# smartbedlight2_5.net
KiCad netlist of a schematic drawn in EAGLE
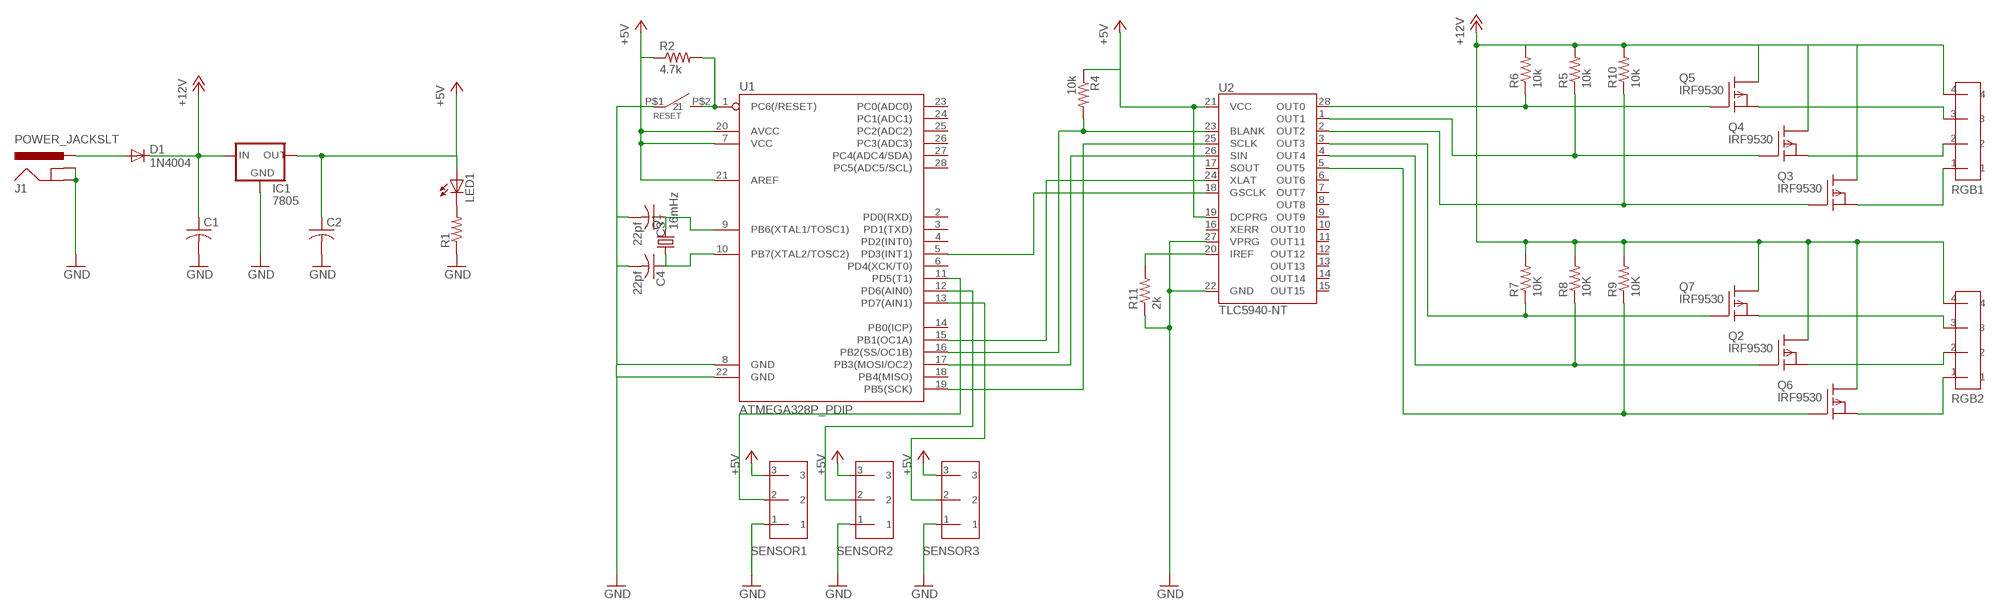
[diagram p0: schematic, sheet 1]

(export (version "E")
  (design (tool "Eeschema 10.0.6"))
  (components
    (comp (ref "C1")
      (value "C-US025-030X050")
      (footprint "eagle-import:C025-030X050")
      (libsource (lib "eagle-import") (part "C-US025-030X050"))
    )
    (comp (ref "C2")
      (value "C-US025-030X050")
      (footprint "eagle-import:C025-030X050")
      (libsource (lib "eagle-import") (part "C-US025-030X050"))
    )
    (comp (ref "C3")
      (value "22pf")
      (footprint "eagle-import:C025-025X050")
      (libsource (lib "eagle-import") (part "resistor_C-US025-025X050"))
    )
    (comp (ref "C4")
      (value "22pf")
      (footprint "eagle-import:C025-025X050")
      (libsource (lib "eagle-import") (part "resistor_C-US025-025X050"))
    )
    (comp (ref "D1")
      (value "1N4004")
      (footprint "eagle-import:DO41-10")
      (libsource (lib "eagle-import") (part "1N4004"))
    )
    (comp (ref "IC1")
      (value "7805")
      (footprint "eagle-import:78XXL")
      (libsource (lib "eagle-import") (part "V_REG_78XXSIDE"))
    )
    (comp (ref "J1")
      (value "POWER_JACKSLT")
      (footprint "eagle-import:POWER_JACK_SLOT")
      (libsource (lib "eagle-import") (part "POWER_JACKSLT"))
    )
    (comp (ref "LED1")
      (value "LED5MM")
      (footprint "eagle-import:LED5MM")
      (libsource (lib "eagle-import") (part "LED5MM"))
    )
    (comp (ref "Q1")
      (value "16mHz")
      (footprint "eagle-import:HC49U-V")
      (libsource (lib "eagle-import") (part "CRYSTALHC49U-V"))
    )
    (comp (ref "Q2")
      (value "IRF9530")
      (footprint "eagle-import:TO220")
      (libsource (lib "eagle-import") (part "IRF9530"))
    )
    (comp (ref "Q3")
      (value "IRF9530")
      (footprint "eagle-import:TO220")
      (libsource (lib "eagle-import") (part "IRF9530"))
    )
    (comp (ref "Q4")
      (value "IRF9530")
      (footprint "eagle-import:TO220")
      (libsource (lib "eagle-import") (part "IRF9530"))
    )
    (comp (ref "Q5")
      (value "IRF9530")
      (footprint "eagle-import:TO220")
      (libsource (lib "eagle-import") (part "IRF9530"))
    )
    (comp (ref "Q6")
      (value "IRF9530")
      (footprint "eagle-import:TO220")
      (libsource (lib "eagle-import") (part "IRF9530"))
    )
    (comp (ref "Q7")
      (value "IRF9530")
      (footprint "eagle-import:TO220")
      (libsource (lib "eagle-import") (part "IRF9530"))
    )
    (comp (ref "R1")
      (value "R-US_0204/7")
      (footprint "eagle-import:0204_7")
      (libsource (lib "eagle-import") (part "R-US_0204/7"))
    )
    (comp (ref "R2")
      (value "4.7k")
      (footprint "eagle-import:0207_10")
      (libsource (lib "eagle-import") (part "resistor_R-US_0207/10"))
    )
    (comp (ref "R4")
      (value "10k")
      (footprint "eagle-import:0207_10")
      (libsource (lib "eagle-import") (part "resistor_R-US_0207/10"))
    )
    (comp (ref "R5")
      (value "10k")
      (footprint "eagle-import:M0805")
      (libsource (lib "eagle-import") (part "resistor_R-US_M0805"))
    )
    (comp (ref "R6")
      (value "10k")
      (footprint "eagle-import:M0805")
      (libsource (lib "eagle-import") (part "resistor_R-US_M0805"))
    )
    (comp (ref "R7")
      (value "10K")
      (footprint "eagle-import:M0805")
      (libsource (lib "eagle-import") (part "resistor_R-US_M0805"))
    )
    (comp (ref "R8")
      (value "10K")
      (footprint "eagle-import:M0805")
      (libsource (lib "eagle-import") (part "resistor_R-US_M0805"))
    )
    (comp (ref "R9")
      (value "10K")
      (footprint "eagle-import:M0805")
      (libsource (lib "eagle-import") (part "resistor_R-US_M0805"))
    )
    (comp (ref "R10")
      (value "10k")
      (footprint "eagle-import:M0805")
      (libsource (lib "eagle-import") (part "resistor_R-US_M0805"))
    )
    (comp (ref "R11")
      (value "2k")
      (footprint "eagle-import:0207_10")
      (libsource (lib "eagle-import") (part "resistor_R-US_0207/10"))
    )
    (comp (ref "RESET")
      (value "TACK_SWITCH")
      (footprint "eagle-import:TACK_SWITCH")
      (libsource (lib "eagle-import") (part "TACK_SWITCH"))
    )
    (comp (ref "RGB1")
      (value "PINHEAD4")
      (footprint "eagle-import:PINHEAD4")
      (libsource (lib "eagle-import") (part "PINHEAD4"))
    )
    (comp (ref "RGB2")
      (value "PINHEAD4")
      (footprint "eagle-import:PINHEAD4")
      (libsource (lib "eagle-import") (part "PINHEAD4"))
    )
    (comp (ref "SENSOR1")
      (value "PINHEAD3")
      (footprint "eagle-import:PINHEAD")
      (libsource (lib "eagle-import") (part "PINHEAD3"))
    )
    (comp (ref "SENSOR2")
      (value "PINHEAD3")
      (footprint "eagle-import:PINHEAD")
      (libsource (lib "eagle-import") (part "PINHEAD3"))
    )
    (comp (ref "SENSOR3")
      (value "PINHEAD3")
      (footprint "eagle-import:PINHEAD")
      (libsource (lib "eagle-import") (part "PINHEAD3"))
    )
    (comp (ref "U1")
      (value "ATMEGA328P_PDIP")
      (footprint "eagle-import:DIL28-3")
      (libsource (lib "eagle-import") (part "ATMEGA328P_PDIP"))
    )
    (comp (ref "U2")
      (value "TLC5940-NT")
      (footprint "eagle-import:DIL28-3")
      (libsource (lib "eagle-import") (part "TLC5940-NT"))
    )
  )
  (nets
    (net (code "1") (name "+5V") (class "Default")
      (node (ref "C2") (pin "1") (pinfunction "1_1") (pintype "passive"))
      (node (ref "IC1") (pin "OUT") (pinfunction "OUT_OUT") (pintype "output"))
      (node (ref "LED1") (pin "A") (pinfunction "A_A") (pintype "passive"))
      (node (ref "R2") (pin "1") (pinfunction "1_1") (pintype "passive"))
      (node (ref "R4") (pin "1") (pinfunction "1_1") (pintype "passive"))
      (node (ref "SENSOR1") (pin "3") (pinfunction "3_3") (pintype "bidirectional"))
      (node (ref "SENSOR2") (pin "3") (pinfunction "3_3") (pintype "bidirectional"))
      (node (ref "SENSOR3") (pin "3") (pinfunction "3_3") (pintype "bidirectional"))
      (node (ref "U1") (pin "20") (pinfunction "AVCC_20") (pintype "bidirectional"))
      (node (ref "U1") (pin "21") (pinfunction "AREF_21") (pintype "bidirectional"))
      (node (ref "U1") (pin "7") (pinfunction "VCC_7") (pintype "bidirectional"))
      (node (ref "U2") (pin "19") (pinfunction "DCPRG_19") (pintype "bidirectional"))
      (node (ref "U2") (pin "21") (pinfunction "VCC_21") (pintype "bidirectional"))
    )
    (net (code "2") (name "+12V") (class "Default")
      (node (ref "C1") (pin "1") (pinfunction "1_1") (pintype "passive"))
      (node (ref "D1") (pin "C") (pinfunction "C_C") (pintype "passive"))
      (node (ref "IC1") (pin "IN") (pinfunction "IN_IN") (pintype "input"))
      (node (ref "Q2") (pin "2") (pinfunction "D_2") (pintype "passive"))
      (node (ref "Q3") (pin "2") (pinfunction "D_2") (pintype "passive"))
      (node (ref "Q4") (pin "2") (pinfunction "D_2") (pintype "passive"))
      (node (ref "Q5") (pin "2") (pinfunction "D_2") (pintype "passive"))
      (node (ref "Q6") (pin "2") (pinfunction "D_2") (pintype "passive"))
      (node (ref "Q7") (pin "2") (pinfunction "D_2") (pintype "passive"))
      (node (ref "R10") (pin "2") (pinfunction "2_2") (pintype "passive"))
      (node (ref "R5") (pin "2") (pinfunction "2_2") (pintype "passive"))
      (node (ref "R6") (pin "2") (pinfunction "2_2") (pintype "passive"))
      (node (ref "R7") (pin "2") (pinfunction "2_2") (pintype "passive"))
      (node (ref "R8") (pin "2") (pinfunction "2_2") (pintype "passive"))
      (node (ref "R9") (pin "2") (pinfunction "2_2") (pintype "passive"))
      (node (ref "RGB1") (pin "4") (pinfunction "4_4") (pintype "bidirectional"))
      (node (ref "RGB2") (pin "4") (pinfunction "4_4") (pintype "bidirectional"))
    )
    (net (code "3") (name "GND") (class "Default")
      (node (ref "C1") (pin "2") (pinfunction "2_2") (pintype "passive"))
      (node (ref "C2") (pin "2") (pinfunction "2_2") (pintype "passive"))
      (node (ref "C3") (pin "2") (pinfunction "2_2") (pintype "passive"))
      (node (ref "C4") (pin "2") (pinfunction "2_2") (pintype "passive"))
      (node (ref "IC1") (pin "GND") (pinfunction "GND_GND") (pintype "input"))
      (node (ref "J1") (pin "GND@1") (pinfunction "GNDBREAK_GND@1") (pintype "bidirectional"))
      (node (ref "J1") (pin "GND@2") (pinfunction "GND_GND@2") (pintype "bidirectional"))
      (node (ref "R1") (pin "1") (pinfunction "1_1") (pintype "passive"))
      (node (ref "R11") (pin "1") (pinfunction "1_1") (pintype "passive"))
      (node (ref "RESET") (pin "P$1") (pinfunction "1_P$1") (pintype "bidirectional"))
      (node (ref "SENSOR1") (pin "1") (pinfunction "1_1") (pintype "bidirectional"))
      (node (ref "SENSOR2") (pin "1") (pinfunction "1_1") (pintype "bidirectional"))
      (node (ref "SENSOR3") (pin "1") (pinfunction "1_1") (pintype "bidirectional"))
      (node (ref "U1") (pin "22") (pinfunction "GND_22") (pintype "bidirectional"))
      (node (ref "U1") (pin "8") (pinfunction "GND_8") (pintype "bidirectional"))
      (node (ref "U2") (pin "22") (pinfunction "GND_22") (pintype "bidirectional"))
      (node (ref "U2") (pin "27") (pinfunction "VPRG_27") (pintype "bidirectional"))
    )
    (net (code "4") (name "Net-(D1-PadA)") (class "Default")
      (node (ref "D1") (pin "A") (pinfunction "A_A") (pintype "passive"))
      (node (ref "J1") (pin "PWR") (pinfunction "PWR_PWR") (pintype "bidirectional"))
    )
    (net (code "5") (name "Net-(LED1-C)") (class "Default")
      (node (ref "LED1") (pin "K") (pinfunction "C_K") (pintype "passive"))
      (node (ref "R1") (pin "2") (pinfunction "2_2") (pintype "passive"))
    )
    (net (code "6") (name "Net-(Q2-G)") (class "Default")
      (node (ref "Q2") (pin "1") (pinfunction "G_1") (pintype "passive"))
      (node (ref "R8") (pin "1") (pinfunction "1_1") (pintype "passive"))
      (node (ref "U2") (pin "4") (pinfunction "OUT4_4") (pintype "bidirectional"))
    )
    (net (code "7") (name "Net-(Q2-S)") (class "Default")
      (node (ref "Q2") (pin "3") (pinfunction "S_3") (pintype "passive"))
      (node (ref "RGB2") (pin "2") (pinfunction "2_2") (pintype "bidirectional"))
    )
    (net (code "8") (name "Net-(Q3-G)") (class "Default")
      (node (ref "Q3") (pin "1") (pinfunction "G_1") (pintype "passive"))
      (node (ref "R10") (pin "1") (pinfunction "1_1") (pintype "passive"))
      (node (ref "U2") (pin "2") (pinfunction "OUT2_2") (pintype "bidirectional"))
    )
    (net (code "9") (name "Net-(Q3-S)") (class "Default")
      (node (ref "Q3") (pin "3") (pinfunction "S_3") (pintype "passive"))
      (node (ref "RGB1") (pin "1") (pinfunction "1_1") (pintype "bidirectional"))
    )
    (net (code "10") (name "Net-(Q4-G)") (class "Default")
      (node (ref "Q4") (pin "1") (pinfunction "G_1") (pintype "passive"))
      (node (ref "R5") (pin "1") (pinfunction "1_1") (pintype "passive"))
      (node (ref "U2") (pin "1") (pinfunction "OUT1_1") (pintype "bidirectional"))
    )
    (net (code "11") (name "Net-(Q4-S)") (class "Default")
      (node (ref "Q4") (pin "3") (pinfunction "S_3") (pintype "passive"))
      (node (ref "RGB1") (pin "2") (pinfunction "2_2") (pintype "bidirectional"))
    )
    (net (code "12") (name "Net-(Q5-G)") (class "Default")
      (node (ref "Q5") (pin "1") (pinfunction "G_1") (pintype "passive"))
      (node (ref "R6") (pin "1") (pinfunction "1_1") (pintype "passive"))
      (node (ref "U2") (pin "28") (pinfunction "OUT0_28") (pintype "bidirectional"))
    )
    (net (code "13") (name "Net-(Q5-S)") (class "Default")
      (node (ref "Q5") (pin "3") (pinfunction "S_3") (pintype "passive"))
      (node (ref "RGB1") (pin "3") (pinfunction "3_3") (pintype "bidirectional"))
    )
    (net (code "14") (name "Net-(Q6-G)") (class "Default")
      (node (ref "Q6") (pin "1") (pinfunction "G_1") (pintype "passive"))
      (node (ref "R9") (pin "1") (pinfunction "1_1") (pintype "passive"))
      (node (ref "U2") (pin "5") (pinfunction "OUT5_5") (pintype "bidirectional"))
    )
    (net (code "15") (name "Net-(Q6-S)") (class "Default")
      (node (ref "Q6") (pin "3") (pinfunction "S_3") (pintype "passive"))
      (node (ref "RGB2") (pin "1") (pinfunction "1_1") (pintype "bidirectional"))
    )
    (net (code "16") (name "Net-(Q7-G)") (class "Default")
      (node (ref "Q7") (pin "1") (pinfunction "G_1") (pintype "passive"))
      (node (ref "R7") (pin "1") (pinfunction "1_1") (pintype "passive"))
      (node (ref "U2") (pin "3") (pinfunction "OUT3_3") (pintype "bidirectional"))
    )
    (net (code "17") (name "Net-(Q7-S)") (class "Default")
      (node (ref "Q7") (pin "3") (pinfunction "S_3") (pintype "passive"))
      (node (ref "RGB2") (pin "3") (pinfunction "3_3") (pintype "bidirectional"))
    )
    (net (code "18") (name "Net-(RESET-2)") (class "Default")
      (node (ref "R2") (pin "2") (pinfunction "2_2") (pintype "passive"))
      (node (ref "RESET") (pin "P$2") (pinfunction "2_P$2") (pintype "bidirectional"))
      (node (ref "U1") (pin "1") (pinfunction "PC6(/RESET)_1") (pintype "bidirectional"))
    )
    (net (code "19") (name "Net-(U1-PB1(OC1A))") (class "Default")
      (node (ref "U1") (pin "15") (pinfunction "PB1(OC1A)_15") (pintype "bidirectional"))
      (node (ref "U2") (pin "24") (pinfunction "XLAT_24") (pintype "bidirectional"))
    )
    (net (code "20") (name "Net-(U1-PB2(SS{slash}OC1B))") (class "Default")
      (node (ref "R4") (pin "2") (pinfunction "2_2") (pintype "passive"))
      (node (ref "U1") (pin "16") (pinfunction "PB2(SS/OC1B)_16") (pintype "bidirectional"))
      (node (ref "U2") (pin "23") (pinfunction "BLANK_23") (pintype "bidirectional"))
    )
    (net (code "21") (name "Net-(U1-PB3(MOSI{slash}OC2))") (class "Default")
      (node (ref "U1") (pin "17") (pinfunction "PB3(MOSI/OC2)_17") (pintype "bidirectional"))
      (node (ref "U2") (pin "26") (pinfunction "SIN_26") (pintype "bidirectional"))
    )
    (net (code "22") (name "Net-(U1-PB5(SCK))") (class "Default")
      (node (ref "U1") (pin "19") (pinfunction "PB5(SCK)_19") (pintype "bidirectional"))
      (node (ref "U2") (pin "25") (pinfunction "SCLK_25") (pintype "bidirectional"))
    )
    (net (code "23") (name "Net-(U1-PB6(XTAL1{slash}TOSC1))") (class "Default")
      (node (ref "C3") (pin "1") (pinfunction "1_1") (pintype "passive"))
      (node (ref "Q1") (pin "2") (pinfunction "2_2") (pintype "passive"))
      (node (ref "U1") (pin "9") (pinfunction "PB6(XTAL1/TOSC1)_9") (pintype "bidirectional"))
    )
    (net (code "24") (name "Net-(U1-PB7(XTAL2{slash}TOSC2))") (class "Default")
      (node (ref "C4") (pin "1") (pinfunction "1_1") (pintype "passive"))
      (node (ref "Q1") (pin "1") (pinfunction "1_1") (pintype "passive"))
      (node (ref "U1") (pin "10") (pinfunction "PB7(XTAL2/TOSC2)_10") (pintype "bidirectional"))
    )
    (net (code "25") (name "Net-(U1-PD3(INT1))") (class "Default")
      (node (ref "U1") (pin "5") (pinfunction "PD3(INT1)_5") (pintype "bidirectional"))
      (node (ref "U2") (pin "18") (pinfunction "GSCLK_18") (pintype "bidirectional"))
    )
    (net (code "26") (name "Net-(U1-PD5(T1))") (class "Default")
      (node (ref "SENSOR1") (pin "2") (pinfunction "2_2") (pintype "bidirectional"))
      (node (ref "U1") (pin "11") (pinfunction "PD5(T1)_11") (pintype "bidirectional"))
    )
    (net (code "27") (name "Net-(U1-PD6(AIN0))") (class "Default")
      (node (ref "SENSOR2") (pin "2") (pinfunction "2_2") (pintype "bidirectional"))
      (node (ref "U1") (pin "12") (pinfunction "PD6(AIN0)_12") (pintype "bidirectional"))
    )
    (net (code "28") (name "Net-(U1-PD7(AIN1))") (class "Default")
      (node (ref "SENSOR3") (pin "2") (pinfunction "2_2") (pintype "bidirectional"))
      (node (ref "U1") (pin "13") (pinfunction "PD7(AIN1)_13") (pintype "bidirectional"))
    )
    (net (code "29") (name "Net-(U2-IREF)") (class "Default")
      (node (ref "R11") (pin "2") (pinfunction "2_2") (pintype "passive"))
      (node (ref "U2") (pin "20") (pinfunction "IREF_20") (pintype "bidirectional"))
    )
    (net (code "30") (name "unconnected-(U1-PB0(ICP)-Pad14)") (class "Default")
      (node (ref "U1") (pin "14") (pinfunction "PB0(ICP)_14") (pintype "bidirectional"))
    )
    (net (code "31") (name "unconnected-(U1-PB4(MISO)-Pad18)") (class "Default")
      (node (ref "U1") (pin "18") (pinfunction "PB4(MISO)_18") (pintype "bidirectional"))
    )
    (net (code "32") (name "unconnected-(U1-PC0(ADC0)-Pad23)") (class "Default")
      (node (ref "U1") (pin "23") (pinfunction "PC0(ADC0)_23") (pintype "bidirectional"))
    )
    (net (code "33") (name "unconnected-(U1-PC1(ADC1)-Pad24)") (class "Default")
      (node (ref "U1") (pin "24") (pinfunction "PC1(ADC1)_24") (pintype "bidirectional"))
    )
    (net (code "34") (name "unconnected-(U1-PC2(ADC2)-Pad25)") (class "Default")
      (node (ref "U1") (pin "25") (pinfunction "PC2(ADC2)_25") (pintype "bidirectional"))
    )
    (net (code "35") (name "unconnected-(U1-PC3(ADC3)-Pad26)") (class "Default")
      (node (ref "U1") (pin "26") (pinfunction "PC3(ADC3)_26") (pintype "bidirectional"))
    )
    (net (code "36") (name "unconnected-(U1-PC4(ADC4{slash}SDA)-Pad27)") (class "Default")
      (node (ref "U1") (pin "27") (pinfunction "PC4(ADC4/SDA)_27") (pintype "bidirectional"))
    )
    (net (code "37") (name "unconnected-(U1-PC5(ADC5{slash}SCL)-Pad28)") (class "Default")
      (node (ref "U1") (pin "28") (pinfunction "PC5(ADC5/SCL)_28") (pintype "bidirectional"))
    )
    (net (code "38") (name "unconnected-(U1-PD0(RXD)-Pad2)") (class "Default")
      (node (ref "U1") (pin "2") (pinfunction "PD0(RXD)_2") (pintype "bidirectional"))
    )
    (net (code "39") (name "unconnected-(U1-PD1(TXD)-Pad3)") (class "Default")
      (node (ref "U1") (pin "3") (pinfunction "PD1(TXD)_3") (pintype "bidirectional"))
    )
    (net (code "40") (name "unconnected-(U1-PD2(INT0)-Pad4)") (class "Default")
      (node (ref "U1") (pin "4") (pinfunction "PD2(INT0)_4") (pintype "bidirectional"))
    )
    (net (code "41") (name "unconnected-(U1-PD4(XCK{slash}T0)-Pad6)") (class "Default")
      (node (ref "U1") (pin "6") (pinfunction "PD4(XCK/T0)_6") (pintype "bidirectional"))
    )
    (net (code "42") (name "unconnected-(U2-OUT6-Pad6)") (class "Default")
      (node (ref "U2") (pin "6") (pinfunction "OUT6_6") (pintype "bidirectional"))
    )
    (net (code "43") (name "unconnected-(U2-OUT7-Pad7)") (class "Default")
      (node (ref "U2") (pin "7") (pinfunction "OUT7_7") (pintype "bidirectional"))
    )
    (net (code "44") (name "unconnected-(U2-OUT8-Pad8)") (class "Default")
      (node (ref "U2") (pin "8") (pinfunction "OUT8_8") (pintype "bidirectional"))
    )
    (net (code "45") (name "unconnected-(U2-OUT9-Pad9)") (class "Default")
      (node (ref "U2") (pin "9") (pinfunction "OUT9_9") (pintype "bidirectional"))
    )
    (net (code "46") (name "unconnected-(U2-OUT10-Pad10)") (class "Default")
      (node (ref "U2") (pin "10") (pinfunction "OUT10_10") (pintype "bidirectional"))
    )
    (net (code "47") (name "unconnected-(U2-OUT11-Pad11)") (class "Default")
      (node (ref "U2") (pin "11") (pinfunction "OUT11_11") (pintype "bidirectional"))
    )
    (net (code "48") (name "unconnected-(U2-OUT12-Pad12)") (class "Default")
      (node (ref "U2") (pin "12") (pinfunction "OUT12_12") (pintype "bidirectional"))
    )
    (net (code "49") (name "unconnected-(U2-OUT13-Pad13)") (class "Default")
      (node (ref "U2") (pin "13") (pinfunction "OUT13_13") (pintype "bidirectional"))
    )
    (net (code "50") (name "unconnected-(U2-OUT14-Pad14)") (class "Default")
      (node (ref "U2") (pin "14") (pinfunction "OUT14_14") (pintype "bidirectional"))
    )
    (net (code "51") (name "unconnected-(U2-OUT15-Pad15)") (class "Default")
      (node (ref "U2") (pin "15") (pinfunction "OUT15_15") (pintype "bidirectional"))
    )
    (net (code "52") (name "unconnected-(U2-SOUT-Pad17)") (class "Default")
      (node (ref "U2") (pin "17") (pinfunction "SOUT_17") (pintype "bidirectional"))
    )
    (net (code "53") (name "unconnected-(U2-XERR-Pad16)") (class "Default")
      (node (ref "U2") (pin "16") (pinfunction "XERR_16") (pintype "bidirectional"))
    )
  )
)
